# hv_bleed.net
KiCad netlist of a schematic drawn in Altium Designer
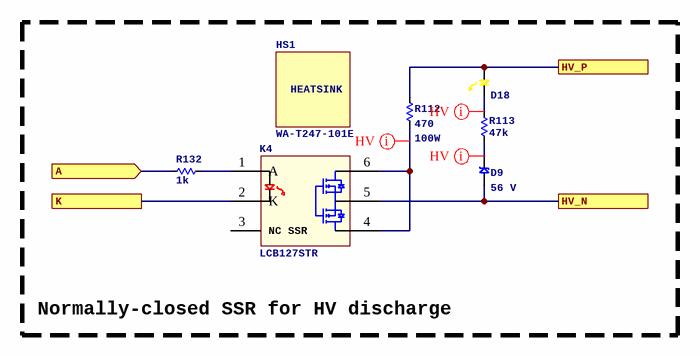
[diagram p0: hv_bleed.SchDoc]

(export (version "E")
  (design (tool "Eeschema 10.0.6"))
  (components
    (comp (ref "D9")
      (value "MM3Z56VC")
      (footprint "SOD323")
      (description "DIODE ZENER 56V 200MW SOD")
      (fields (field (name "MANUFACTURER") "onsemi") (field (name "VOLTAGE - ZENER (NOM) (VZ)") "56 V"))
      (libsource (lib "SSCP") (part "ZENER_MM3Z56VC"))
    )
    (comp (ref "D18")
      (value "LTST-C190YKT")
      (footprint "LED_0603P_YELLOW")
      (description "LED YELLOW CLEAR 0603 SMD")
      (fields (field (name "MANUFACTURER") "Lite-On Inc"))
      (libsource (lib "SSCP") (part "LED_0603_YELLOW_LTST-C190YKT"))
    )
    (comp (ref "HS1")
      (value "WA-T247-101E")
      (footprint "OHMITE_WA-T247-101E")
      (description "Heat Sink, 11ohm, Extruded, Clip, Longitudinal, Aluminum Alloy, Anodized")
      (fields (field (name "MANUFACTURER") "Ohmite"))
      (libsource (lib "SSCP") (part "HEATSINK_OHMITE_WA-T247-101E"))
    )
    (comp (ref "K4")
      (value "LCB127STR")
      (footprint "6SMD300")
      (description "Relay Ssr 50MA 1.4V Dc-in 0.2A 250V Ac/dc-out 6-PIN PDIP SMD T/r")
      (fields (field (name "MANUFACTURER") "IXYS"))
      (libsource (lib "SSCP") (part "SSR_250V_LCB127STR"))
    )
    (comp (ref "R112")
      (value "TEH100M470RJE")
      (footprint "TO-247-2_VERTICAL")
      (description "RES TK FM 470 OHM 100W 1% TO247")
      (fields
        (field (name "MANUFACTURER") "Ohmite")
        (field (name "RESISTANCE (OHMS)") "470")
        (field (name "POWER (WATTS)") "100W")
      )
      (libsource (lib "SSCP") (part "RES_470_OHM_100W_1%_TO247"))
    )
    (comp (ref "R113")
      (value "47k")
      (footprint "R0402")
      (fields
        (field (name "MANUFACTURER PART NUMBER") "0402WGF4702TCE")
        (field (name "MANUFACTURER") "UNI-ROYAL(Uniroyal Elec)")
        (field (name "TOLERANCE") "1%")
      )
      (libsource (lib "database") (part "__template_resistor"))
    )
    (comp (ref "R132")
      (value "1k")
      (footprint "R0402")
      (fields
        (field (name "TOLERANCE") "1%")
        (field (name "MANUFACTURER PART NUMBER") "0402WGF1001TCE")
        (field (name "MANUFACTURER") "UNI-ROYAL(Uniroyal Elec)")
      )
      (libsource (lib "database") (part "__template_resistor"))
    )
  )
  (nets
    (net (code "1") (name "/A") (class "Default") (node (ref "R132") (pin "2") (pintype "passive")))
    (net (code "2") (name "/HV_N") (class "Default")
      (node (ref "D9") (pin "1") (pintype "passive"))
      (node (ref "K4") (pin "5") (pintype "passive"))
    )
    (net (code "3") (name "/HV_P") (class "Default")
      (node (ref "D18") (pin "2") (pintype "passive"))
      (node (ref "R112") (pin "2") (pintype "passive"))
    )
    (net (code "4") (name "/K") (class "Default")
      (node (ref "K4") (pin "2") (pinfunction "K_2") (pintype "passive"))
    )
    (net (code "5") (name "Net-(D9-Pad2)") (class "Default")
      (node (ref "D9") (pin "2") (pintype "passive"))
      (node (ref "R113") (pin "2") (pintype "passive"))
    )
    (net (code "6") (name "Net-(D18-Pad1)") (class "Default")
      (node (ref "D18") (pin "1") (pintype "passive"))
      (node (ref "R113") (pin "1") (pintype "passive"))
    )
    (net (code "7") (name "Net-(K4-A)") (class "Default")
      (node (ref "K4") (pin "1") (pinfunction "A_1") (pintype "passive"))
      (node (ref "R132") (pin "1") (pintype "passive"))
    )
    (net (code "8") (name "Net-(K4-Pad4)") (class "Default")
      (node (ref "K4") (pin "4") (pintype "passive"))
      (node (ref "K4") (pin "6") (pintype "passive"))
      (node (ref "R112") (pin "1") (pintype "passive"))
    )
    (net (code "9") (name "unconnected-(K4-Pad3)") (class "Default")
      (node (ref "K4") (pin "3") (pintype "passive"))
    )
  )
)
